# Display_Board_v3.net
KiCad netlist of a schematic drawn in EAGLE
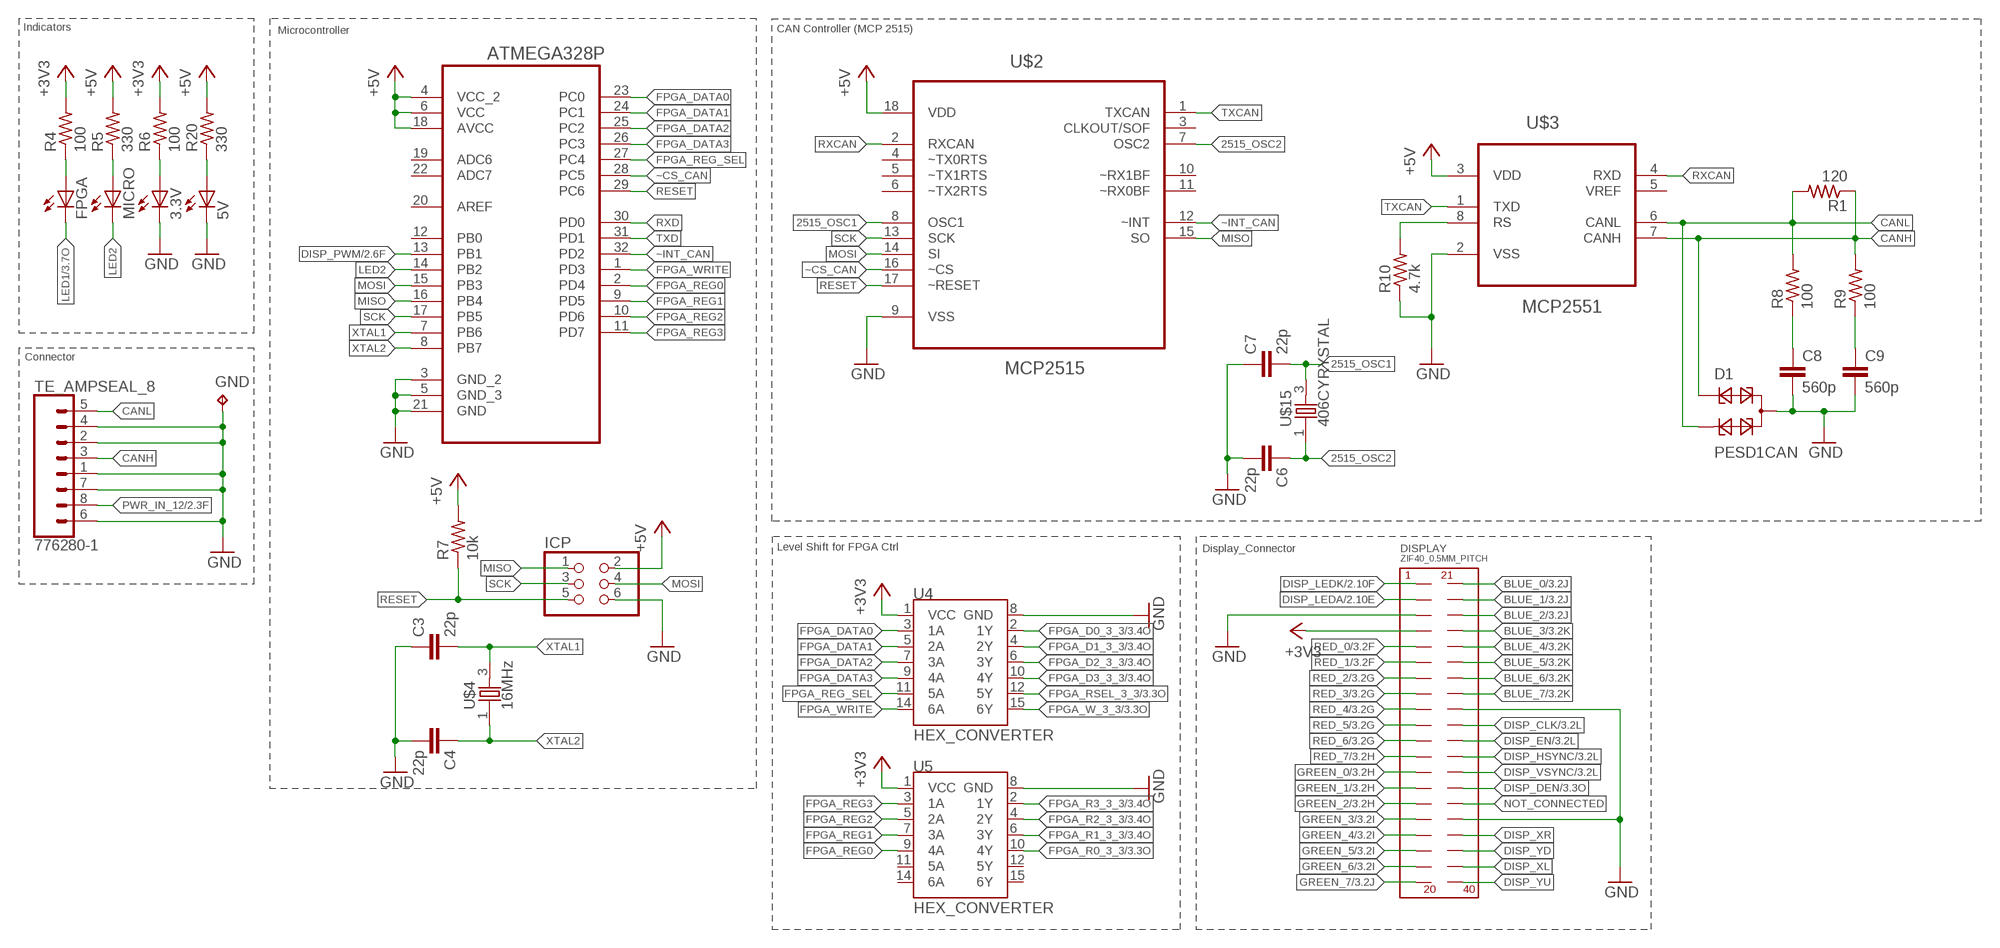
[diagram p0: schematic, sheet 1]
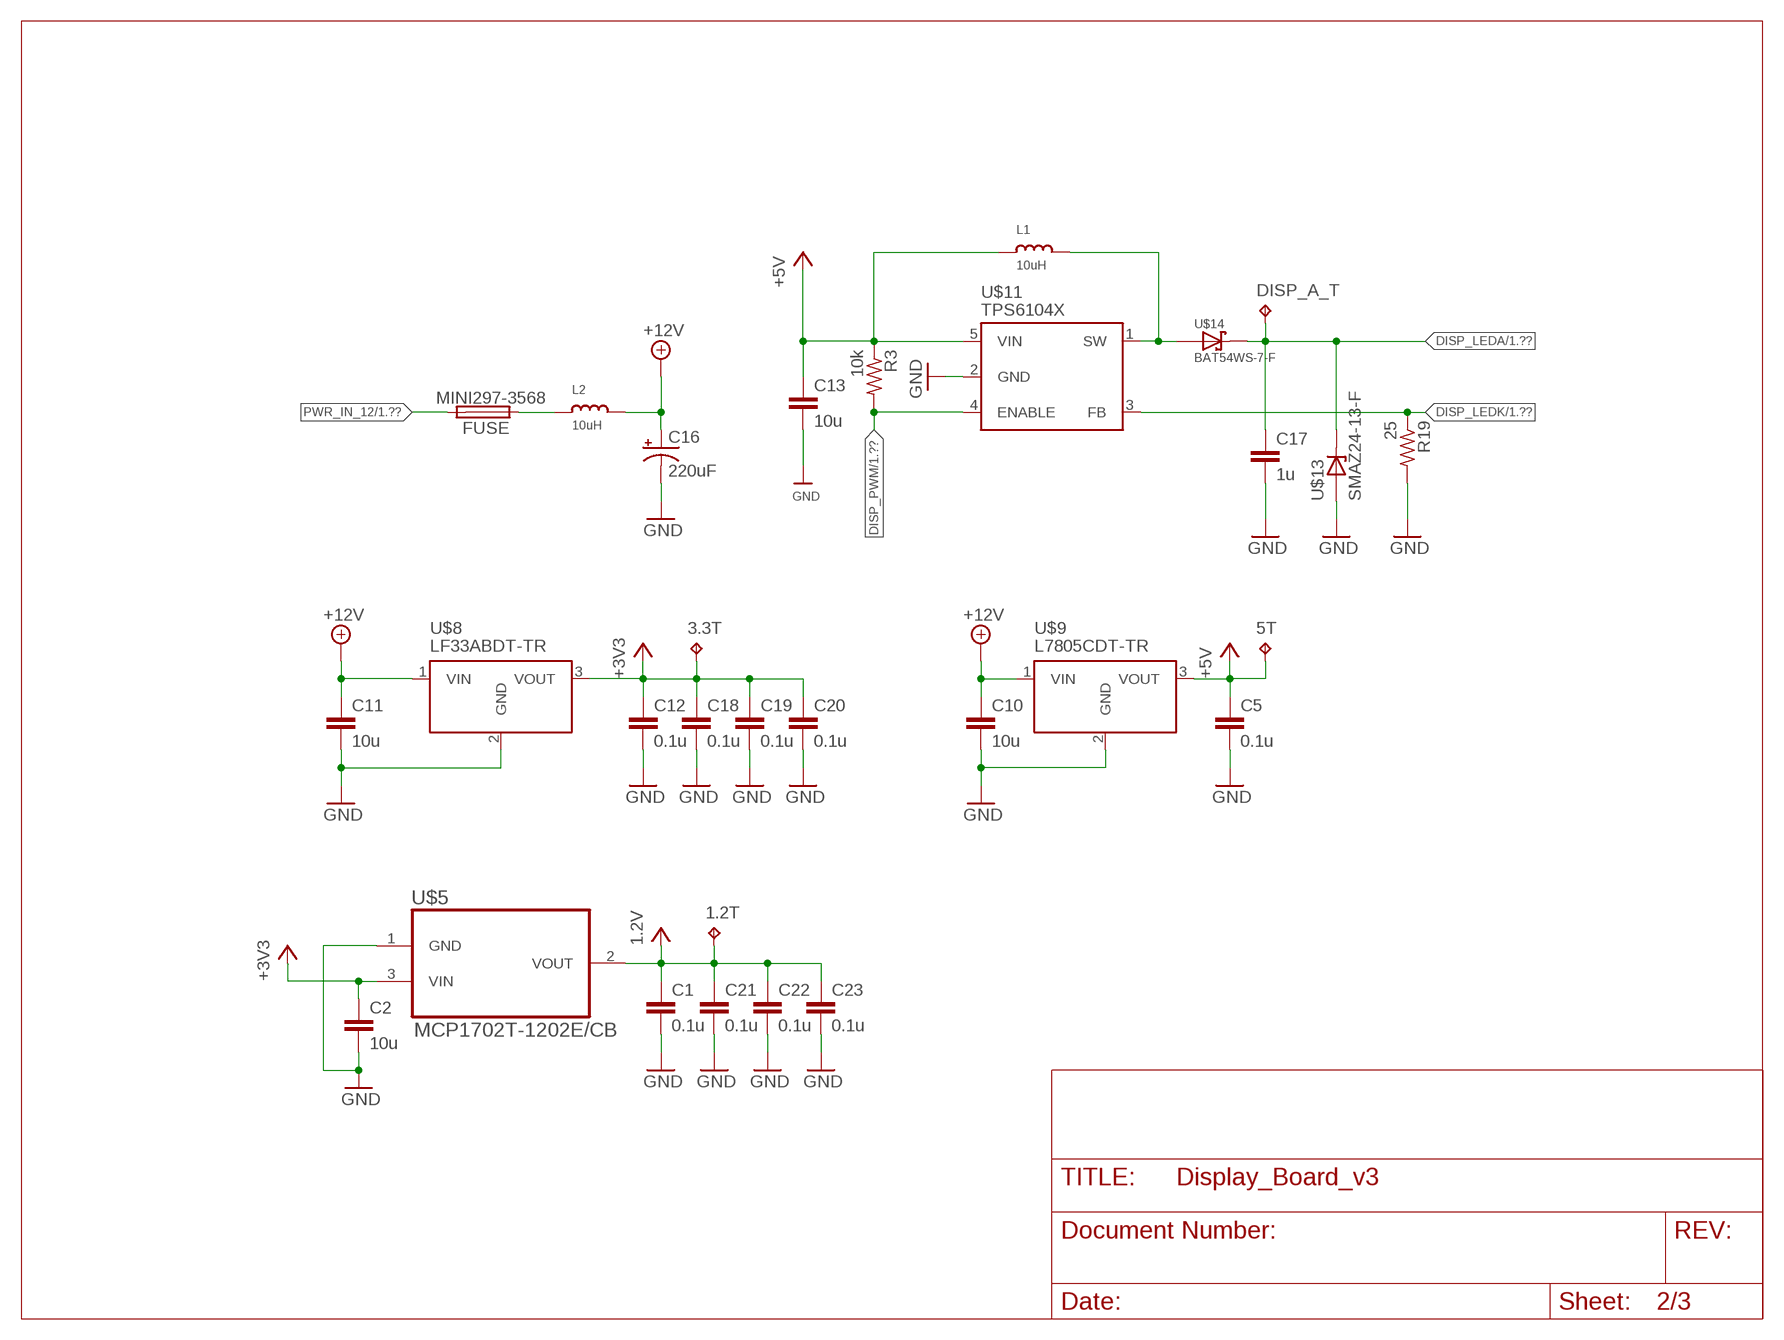
[diagram p1: schematic, sheet 2]
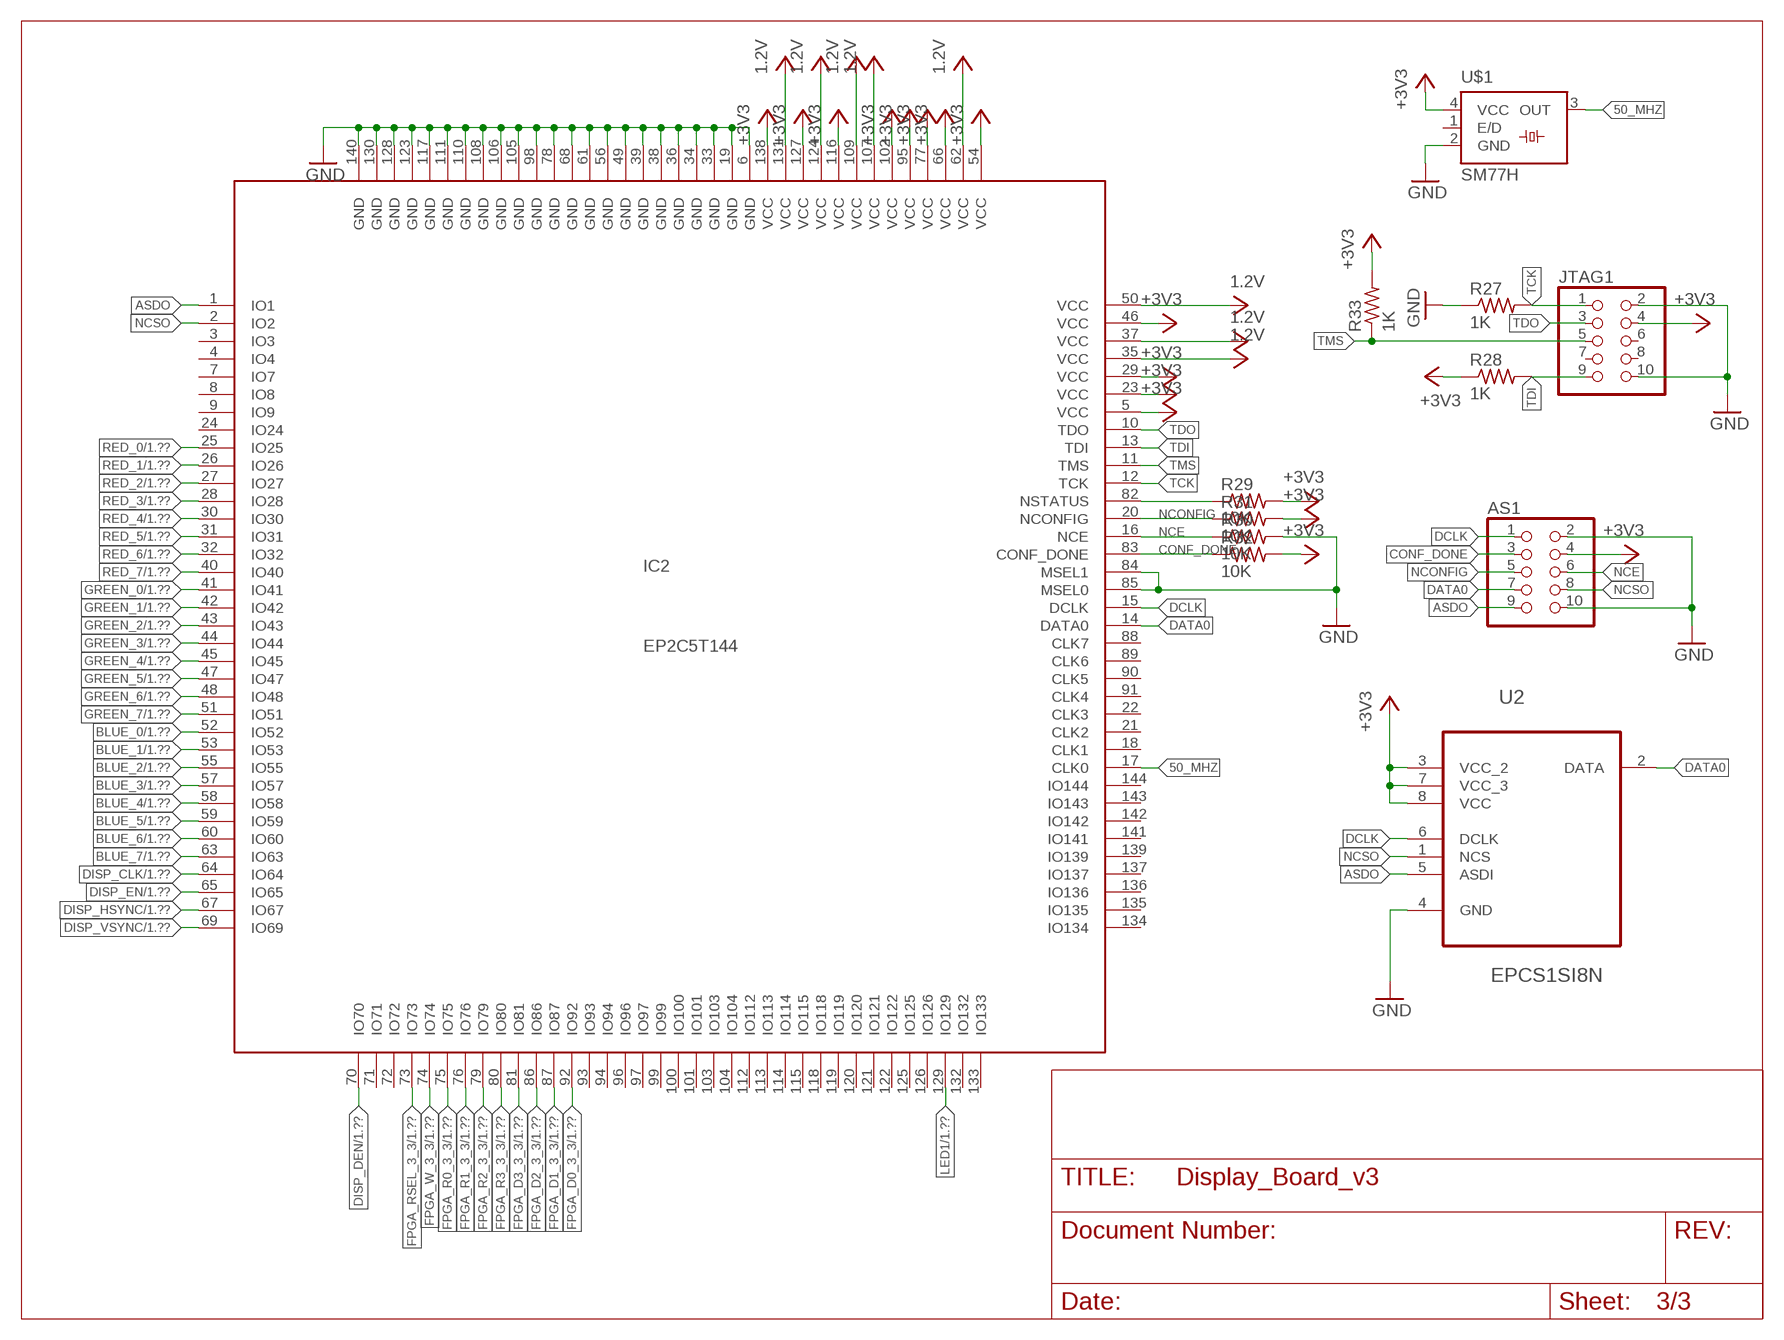
[diagram p2: schematic, sheet 3]

(export (version "E")
  (design (tool "Eeschema 10.0.6"))
  (components
    (comp (ref "3.3V")
      (value "LEDCHIP-LED0805")
      (footprint "eagle-import:CHIP-LED0805")
      (libsource (lib "eagle-import") (part "LEDCHIP-LED0805"))
    )
    (comp (ref "5V")
      (value "LEDCHIP-LED0805")
      (footprint "eagle-import:CHIP-LED0805")
      (libsource (lib "eagle-import") (part "LEDCHIP-LED0805"))
    )
    (comp (ref "ATMEGA328P")
      (value "ATMEGA328P-AU")
      (footprint "eagle-import:QFP80P900X900X120-32N")
      (libsource (lib "eagle-import") (part "ATMEGA328P-AU"))
    )
    (comp (ref "C3")
      (value "22p")
      (footprint "eagle-import:C0805K")
      (libsource (lib "eagle-import") (part "resistor_C-EUC0805K"))
    )
    (comp (ref "C4")
      (value "22p")
      (footprint "eagle-import:C0805K")
      (libsource (lib "eagle-import") (part "resistor_C-EUC0805K"))
    )
    (comp (ref "C6")
      (value "22p")
      (footprint "eagle-import:C0805K")
      (libsource (lib "eagle-import") (part "resistor_C-EUC0805K"))
    )
    (comp (ref "C7")
      (value "22p")
      (footprint "eagle-import:C0805K")
      (libsource (lib "eagle-import") (part "resistor_C-EUC0805K"))
    )
    (comp (ref "C8")
      (value "560p")
      (footprint "eagle-import:C0805K")
      (libsource (lib "eagle-import") (part "C-EUC0805K"))
    )
    (comp (ref "C9")
      (value "560p")
      (footprint "eagle-import:C0805K")
      (libsource (lib "eagle-import") (part "C-EUC0805K"))
    )
    (comp (ref "D1")
      (value "PESD1CAN")
      (footprint "eagle-import:SOT23")
      (libsource (lib "eagle-import") (part "PESD1CAN"))
    )
    (comp (ref "DISPLAY")
      (value "ZIF40_0.5MM_PITCH")
      (footprint "eagle-import:ZIF40")
      (libsource (lib "eagle-import") (part "ZIF40_0.5MM_PITCH"))
    )
    (comp (ref "FPGA")
      (value "LEDCHIP-LED0805")
      (footprint "eagle-import:CHIP-LED0805")
      (libsource (lib "eagle-import") (part "LEDCHIP-LED0805"))
    )
    (comp (ref "GND")
      (value "TPTP12SQ")
      (footprint "eagle-import:TP12SQ")
      (libsource (lib "eagle-import") (part "TPTP12SQ"))
    )
    (comp (ref "ICP")
      (value "PINHD-2X3")
      (footprint "eagle-import:2X03")
      (libsource (lib "eagle-import") (part "PINHD-2X3"))
    )
    (comp (ref "MICRO")
      (value "LEDCHIP-LED0805")
      (footprint "eagle-import:CHIP-LED0805")
      (libsource (lib "eagle-import") (part "LEDCHIP-LED0805"))
    )
    (comp (ref "R1")
      (value "120")
      (footprint "eagle-import:R0805")
      (libsource (lib "eagle-import") (part "R-US_R0805"))
    )
    (comp (ref "R4")
      (value "100")
      (footprint "eagle-import:R0805")
      (libsource (lib "eagle-import") (part "resistor_R-US_R0805"))
    )
    (comp (ref "R5")
      (value "330")
      (footprint "eagle-import:R0805")
      (libsource (lib "eagle-import") (part "resistor_R-US_R0805"))
    )
    (comp (ref "R6")
      (value "100")
      (footprint "eagle-import:R0805")
      (libsource (lib "eagle-import") (part "resistor_R-US_R0805"))
    )
    (comp (ref "R7")
      (value "10k")
      (footprint "eagle-import:R0805")
      (libsource (lib "eagle-import") (part "R-US_R0805"))
    )
    (comp (ref "R8")
      (value "100")
      (footprint "eagle-import:R0805")
      (libsource (lib "eagle-import") (part "R-US_R0805"))
    )
    (comp (ref "R9")
      (value "100")
      (footprint "eagle-import:R0805")
      (libsource (lib "eagle-import") (part "R-US_R0805"))
    )
    (comp (ref "R10")
      (value "4.7k")
      (footprint "eagle-import:R0805")
      (libsource (lib "eagle-import") (part "R-US_R0805"))
    )
    (comp (ref "R20")
      (value "330")
      (footprint "eagle-import:R0805")
      (libsource (lib "eagle-import") (part "resistor_R-US_R0805"))
    )
    (comp (ref "TE_AMPSEAL_8")
      (value "776280-1")
      (footprint "eagle-import:776280-1")
      (libsource (lib "eagle-import") (part "776280-1"))
    )
    (comp (ref "U$2")
      (value "MCP2515")
      (footprint "eagle-import:SOIC127P1034X264-18N")
      (fields (field (name "MPN") "MCP2515-I/SO"))
      (libsource (lib "eagle-import") (part "MCP2515-I/SO"))
    )
    (comp (ref "U$3")
      (value "MCP2551")
      (footprint "eagle-import:SOIC127P600X175-8N")
      (fields (field (name "MPN") "MCP2551-I/SN"))
      (libsource (lib "eagle-import") (part "MCP2551-I/SN"))
    )
    (comp (ref "U$4")
      (value "16MHz")
      (footprint "eagle-import:CTS406")
      (libsource (lib "eagle-import") (part "406CYRYSTAL"))
    )
    (comp (ref "U$15")
      (value "406CYRYSTAL")
      (footprint "eagle-import:CTS406")
      (libsource (lib "eagle-import") (part "406CYRYSTAL"))
    )
    (comp (ref "U4")
      (value "HEX_CONVERTER")
      (footprint "eagle-import:SO016")
      (libsource (lib "eagle-import") (part "HEX_CONVERTER"))
    )
    (comp (ref "U5")
      (value "HEX_CONVERTER")
      (footprint "eagle-import:SO016")
      (libsource (lib "eagle-import") (part "HEX_CONVERTER"))
    )
    (comp (ref "AS1")
      (value "PINHD-2X5")
      (footprint "eagle-import:2X05")
      (libsource (lib "eagle-import") (part "PINHD-2X5"))
    )
    (comp (ref "IC2")
      (value "EP2C5T144")
      (footprint "eagle-import:TQFP144")
      (fields (field (name "MPN") "EP2C5T144C8N"))
      (libsource (lib "eagle-import") (part "EP2C5T144"))
    )
    (comp (ref "JTAG1")
      (value "PINHD-2X5")
      (footprint "eagle-import:2X05")
      (libsource (lib "eagle-import") (part "PINHD-2X5"))
    )
    (comp (ref "R27")
      (value "1K")
      (footprint "eagle-import:R0805")
      (libsource (lib "eagle-import") (part "resistor_R-US_R0805"))
    )
    (comp (ref "R28")
      (value "1K")
      (footprint "eagle-import:R0805")
      (libsource (lib "eagle-import") (part "resistor_R-US_R0805"))
    )
    (comp (ref "R29")
      (value "10K")
      (footprint "eagle-import:R0805")
      (libsource (lib "eagle-import") (part "resistor_R-US_R0805"))
    )
    (comp (ref "R30")
      (value "10K")
      (footprint "eagle-import:R0805")
      (libsource (lib "eagle-import") (part "resistor_R-US_R0805"))
    )
    (comp (ref "R31")
      (value "10K")
      (footprint "eagle-import:R0805")
      (libsource (lib "eagle-import") (part "resistor_R-US_R0805"))
    )
    (comp (ref "R32")
      (value "10K")
      (footprint "eagle-import:R0805")
      (libsource (lib "eagle-import") (part "resistor_R-US_R0805"))
    )
    (comp (ref "R33")
      (value "1K")
      (footprint "eagle-import:R0805")
      (libsource (lib "eagle-import") (part "resistor_R-US_R0805"))
    )
    (comp (ref "U$1")
      (value "SM77H")
      (footprint "eagle-import:SM77H")
      (libsource (lib "eagle-import") (part "SM77H"))
    )
    (comp (ref "U2")
      (value "EPCS1SI8N")
      (footprint "eagle-import:SOIC127P600X175-8N")
      (libsource (lib "eagle-import") (part "EPCS1SI8N"))
    )
    (comp (ref "1.2T")
      (value "TPTP12SQ")
      (footprint "eagle-import:TP12SQ")
      (libsource (lib "eagle-import") (part "TPTP12SQ"))
    )
    (comp (ref "3.3T")
      (value "TPTP12SQ")
      (footprint "eagle-import:TP12SQ")
      (libsource (lib "eagle-import") (part "TPTP12SQ"))
    )
    (comp (ref "5T")
      (value "TPTP12SQ")
      (footprint "eagle-import:TP12SQ")
      (libsource (lib "eagle-import") (part "TPTP12SQ"))
    )
    (comp (ref "C1")
      (value "0.1u")
      (footprint "eagle-import:C0805K")
      (libsource (lib "eagle-import") (part "C-EUC0805K"))
    )
    (comp (ref "C2")
      (value "10u")
      (footprint "eagle-import:C0805K")
      (libsource (lib "eagle-import") (part "C-EUC0805K"))
    )
    (comp (ref "C5")
      (value "0.1u")
      (footprint "eagle-import:C0805K")
      (libsource (lib "eagle-import") (part "C-EUC0805K"))
    )
    (comp (ref "C10")
      (value "10u")
      (footprint "eagle-import:C0805K")
      (libsource (lib "eagle-import") (part "C-EUC0805K"))
    )
    (comp (ref "C11")
      (value "10u")
      (footprint "eagle-import:C0805K")
      (libsource (lib "eagle-import") (part "C-EUC0805K"))
    )
    (comp (ref "C12")
      (value "0.1u")
      (footprint "eagle-import:C0805K")
      (libsource (lib "eagle-import") (part "C-EUC0805K"))
    )
    (comp (ref "C13")
      (value "10u")
      (footprint "eagle-import:C0805K")
      (libsource (lib "eagle-import") (part "C-EUC0805K"))
    )
    (comp (ref "C16")
      (value "220uF")
      (footprint "eagle-import:UD-6,3X7,7_NICHICON")
      (libsource (lib "eagle-import") (part "CPOL-USUD-6,3X7,7"))
    )
    (comp (ref "C17")
      (value "1u")
      (footprint "eagle-import:C0805K")
      (libsource (lib "eagle-import") (part "C-EUC0805K"))
    )
    (comp (ref "C18")
      (value "0.1u")
      (footprint "eagle-import:C0805K")
      (libsource (lib "eagle-import") (part "C-EUC0805K"))
    )
    (comp (ref "C19")
      (value "0.1u")
      (footprint "eagle-import:C0805K")
      (libsource (lib "eagle-import") (part "C-EUC0805K"))
    )
    (comp (ref "C20")
      (value "0.1u")
      (footprint "eagle-import:C0805K")
      (libsource (lib "eagle-import") (part "C-EUC0805K"))
    )
    (comp (ref "C21")
      (value "0.1u")
      (footprint "eagle-import:C0805K")
      (libsource (lib "eagle-import") (part "C-EUC0805K"))
    )
    (comp (ref "C22")
      (value "0.1u")
      (footprint "eagle-import:C0805K")
      (libsource (lib "eagle-import") (part "C-EUC0805K"))
    )
    (comp (ref "C23")
      (value "0.1u")
      (footprint "eagle-import:C0805K")
      (libsource (lib "eagle-import") (part "C-EUC0805K"))
    )
    (comp (ref "DISP_A_T")
      (value "TPTP12SQ")
      (footprint "eagle-import:TP12SQ")
      (libsource (lib "eagle-import") (part "TPTP12SQ"))
    )
    (comp (ref "FUSE")
      (value "MINI297-3568")
      (footprint "eagle-import:3568")
      (libsource (lib "eagle-import") (part "MINI297-3568"))
    )
    (comp (ref "L1")
      (value "10uH")
      (footprint "eagle-import:INDUCTOR_5X5MM_NR5040_NOTHERMALS")
      (libsource (lib "eagle-import") (part "INDUCTORNR5040"))
    )
    (comp (ref "L2")
      (value "10uH")
      (footprint "eagle-import:INDUCTOR_5X5MM_NR5040_NOTHERMALS")
      (libsource (lib "eagle-import") (part "INDUCTORNR5040"))
    )
    (comp (ref "R3")
      (value "10k")
      (footprint "eagle-import:R0805")
      (libsource (lib "eagle-import") (part "rcl_334_R-US_R0805"))
    )
    (comp (ref "R19")
      (value "25")
      (footprint "eagle-import:R0805")
      (libsource (lib "eagle-import") (part "rcl_334_R-US_R0805"))
    )
    (comp (ref "U$5")
      (value "MCP1702T-1202E/CB")
      (footprint "eagle-import:SOT95P300X145-3N")
      (fields (field (name "MPN") "MCP1702T-1802E/CB"))
      (libsource (lib "eagle-import") (part "MCP1702T-1802E/CB"))
    )
    (comp (ref "U$8")
      (value "LF33ABDT-TR")
      (footprint "eagle-import:DPACK")
      (libsource (lib "eagle-import") (part "LF33ABDT-TR"))
    )
    (comp (ref "U$9")
      (value "L7805CDT-TR")
      (footprint "eagle-import:DPACK")
      (libsource (lib "eagle-import") (part "L7805CDT-TR"))
    )
    (comp (ref "U$11")
      (value "TPS6104X")
      (footprint "eagle-import:SOT23-5L")
      (libsource (lib "eagle-import") (part "TPS6104X"))
    )
    (comp (ref "U$13")
      (value "SMAZ24-13-F")
      (footprint "eagle-import:SMA_DIODE")
      (libsource (lib "eagle-import") (part "SMAZ24-13-F"))
    )
    (comp (ref "U$14")
      (value "BAT54WS-7-F")
      (footprint "eagle-import:SOD323")
      (libsource (lib "eagle-import") (part "BAT54WS-7-F"))
    )
  )
  (nets
    (net (code "1") (name "+3V3") (class "Default")
      (node (ref "3.3T") (pin "TP") (pinfunction "TP_TP") (pintype "input"))
      (node (ref "AS1") (pin "4") (pinfunction "4_4") (pintype "passive"))
      (node (ref "C12") (pin "1") (pinfunction "1_1") (pintype "passive"))
      (node (ref "C18") (pin "1") (pinfunction "1_1") (pintype "passive"))
      (node (ref "C19") (pin "1") (pinfunction "1_1") (pintype "passive"))
      (node (ref "C2") (pin "1") (pinfunction "1_1") (pintype "passive"))
      (node (ref "C20") (pin "1") (pinfunction "1_1") (pintype "passive"))
      (node (ref "DISPLAY") (pin "P$4") (pinfunction "P$4_P$4") (pintype "bidirectional"))
      (node (ref "IC2") (pin "102") (pinfunction "VCC_102") (pintype "power_in"))
      (node (ref "IC2") (pin "116") (pinfunction "VCC_116") (pintype "power_in"))
      (node (ref "IC2") (pin "127") (pinfunction "VCC_127") (pintype "power_in"))
      (node (ref "IC2") (pin "138") (pinfunction "VCC_138") (pintype "power_in"))
      (node (ref "IC2") (pin "23") (pinfunction "VCC_23") (pintype "power_in"))
      (node (ref "IC2") (pin "29") (pinfunction "VCC_29") (pintype "power_in"))
      (node (ref "IC2") (pin "46") (pinfunction "VCC_46") (pintype "power_in"))
      (node (ref "IC2") (pin "5") (pinfunction "VCC_5") (pintype "power_in"))
      (node (ref "IC2") (pin "54") (pinfunction "VCC_54") (pintype "power_in"))
      (node (ref "IC2") (pin "66") (pinfunction "VCC_66") (pintype "power_in"))
      (node (ref "IC2") (pin "77") (pinfunction "VCC_77") (pintype "power_in"))
      (node (ref "IC2") (pin "95") (pinfunction "VCC_95") (pintype "power_in"))
      (node (ref "JTAG1") (pin "4") (pinfunction "4_4") (pintype "passive"))
      (node (ref "R28") (pin "1") (pinfunction "1_1") (pintype "passive"))
      (node (ref "R29") (pin "2") (pinfunction "2_2") (pintype "passive"))
      (node (ref "R31") (pin "2") (pinfunction "2_2") (pintype "passive"))
      (node (ref "R32") (pin "2") (pinfunction "2_2") (pintype "passive"))
      (node (ref "R33") (pin "2") (pinfunction "2_2") (pintype "passive"))
      (node (ref "R4") (pin "2") (pinfunction "2_2") (pintype "passive"))
      (node (ref "R6") (pin "2") (pinfunction "2_2") (pintype "passive"))
      (node (ref "U$1") (pin "4") (pinfunction "VCC_4") (pintype "power_in"))
      (node (ref "U$5") (pin "3") (pinfunction "VIN_3") (pintype "power_in"))
      (node (ref "U$8") (pin "3") (pinfunction "VOUT_3") (pintype "bidirectional"))
      (node (ref "U2") (pin "3") (pinfunction "VCC_2_3") (pintype "power_in"))
      (node (ref "U2") (pin "7") (pinfunction "VCC_3_7") (pintype "power_in"))
      (node (ref "U2") (pin "8") (pinfunction "VCC_8") (pintype "power_in"))
      (node (ref "U4") (pin "1") (pinfunction "VCC_1") (pintype "bidirectional"))
      (node (ref "U5") (pin "1") (pinfunction "VCC_1") (pintype "bidirectional"))
    )
    (net (code "2") (name "+5V") (class "Default")
      (node (ref "5T") (pin "TP") (pinfunction "TP_TP") (pintype "input"))
      (node (ref "ATMEGA328P") (pin "18") (pinfunction "AVCC_18") (pintype "power_in"))
      (node (ref "ATMEGA328P") (pin "4") (pinfunction "VCC_2_4") (pintype "power_in"))
      (node (ref "ATMEGA328P") (pin "6") (pinfunction "VCC_6") (pintype "power_in"))
      (node (ref "C13") (pin "1") (pinfunction "1_1") (pintype "passive"))
      (node (ref "C5") (pin "1") (pinfunction "1_1") (pintype "passive"))
      (node (ref "ICP") (pin "2") (pinfunction "2_2") (pintype "passive"))
      (node (ref "L1") (pin "P$1") (pinfunction "1_P$1") (pintype "passive"))
      (node (ref "R20") (pin "2") (pinfunction "2_2") (pintype "passive"))
      (node (ref "R3") (pin "1") (pinfunction "1_1") (pintype "passive"))
      (node (ref "R5") (pin "2") (pinfunction "2_2") (pintype "passive"))
      (node (ref "R7") (pin "2") (pinfunction "2_2") (pintype "passive"))
      (node (ref "U$11") (pin "5") (pinfunction "VIN_5") (pintype "bidirectional"))
      (node (ref "U$2") (pin "18") (pinfunction "VDD_18") (pintype "power_in"))
      (node (ref "U$3") (pin "3") (pinfunction "VDD_3") (pintype "power_in"))
      (node (ref "U$9") (pin "3") (pinfunction "VOUT_3") (pintype "bidirectional"))
    )
    (net (code "3") (name "+12V") (class "Default")
      (node (ref "C10") (pin "1") (pinfunction "1_1") (pintype "passive"))
      (node (ref "C11") (pin "1") (pinfunction "1_1") (pintype "passive"))
      (node (ref "C16") (pin "+") (pinfunction "+_+") (pintype "passive"))
      (node (ref "L2") (pin "P$2") (pinfunction "2_P$2") (pintype "passive"))
      (node (ref "U$8") (pin "1") (pinfunction "VIN_1") (pintype "bidirectional"))
      (node (ref "U$9") (pin "1") (pinfunction "VIN_1") (pintype "bidirectional"))
    )
    (net (code "4") (name "50_MHZ") (class "Default")
      (node (ref "IC2") (pin "17") (pinfunction "CLK0_17") (pintype "bidirectional"))
      (node (ref "U$1") (pin "3") (pinfunction "OUT_3") (pintype "output"))
    )
    (net (code "5") (name "2515_OSC1") (class "Default")
      (node (ref "C7") (pin "2") (pinfunction "2_2") (pintype "passive"))
      (node (ref "U$15") (pin "3") (pinfunction "2_3") (pintype "passive"))
      (node (ref "U$2") (pin "8") (pinfunction "OSC1_8") (pintype "input"))
    )
    (net (code "6") (name "2515_OSC2") (class "Default")
      (node (ref "C6") (pin "1") (pinfunction "1_1") (pintype "passive"))
      (node (ref "U$15") (pin "1") (pinfunction "1_1") (pintype "passive"))
      (node (ref "U$2") (pin "7") (pinfunction "OSC2_7") (pintype "output"))
    )
    (net (code "7") (name "ASDO") (class "Default")
      (node (ref "AS1") (pin "9") (pinfunction "9_9") (pintype "passive"))
      (node (ref "IC2") (pin "1") (pinfunction "IO1_1") (pintype "output"))
      (node (ref "U2") (pin "5") (pinfunction "ASDI_5") (pintype "input"))
    )
    (net (code "8") (name "BLUE_0") (class "Default")
      (node (ref "DISPLAY") (pin "P$21") (pinfunction "P$21_P$21") (pintype "bidirectional"))
      (node (ref "IC2") (pin "52") (pinfunction "IO52_52") (pintype "bidirectional"))
    )
    (net (code "9") (name "BLUE_1") (class "Default")
      (node (ref "DISPLAY") (pin "P$22") (pinfunction "P$22_P$22") (pintype "bidirectional"))
      (node (ref "IC2") (pin "53") (pinfunction "IO53_53") (pintype "bidirectional"))
    )
    (net (code "10") (name "BLUE_2") (class "Default")
      (node (ref "DISPLAY") (pin "P$23") (pinfunction "P$23_P$23") (pintype "bidirectional"))
      (node (ref "IC2") (pin "55") (pinfunction "IO55_55") (pintype "bidirectional"))
    )
    (net (code "11") (name "BLUE_3") (class "Default")
      (node (ref "DISPLAY") (pin "P$24") (pinfunction "P$24_P$24") (pintype "bidirectional"))
      (node (ref "IC2") (pin "57") (pinfunction "IO57_57") (pintype "bidirectional"))
    )
    (net (code "12") (name "BLUE_4") (class "Default")
      (node (ref "DISPLAY") (pin "P$25") (pinfunction "P$25_P$25") (pintype "bidirectional"))
      (node (ref "IC2") (pin "58") (pinfunction "IO58_58") (pintype "bidirectional"))
    )
    (net (code "13") (name "BLUE_5") (class "Default")
      (node (ref "DISPLAY") (pin "P$26") (pinfunction "P$26_P$26") (pintype "bidirectional"))
      (node (ref "IC2") (pin "59") (pinfunction "IO59_59") (pintype "bidirectional"))
    )
    (net (code "14") (name "BLUE_6") (class "Default")
      (node (ref "DISPLAY") (pin "P$27") (pinfunction "P$27_P$27") (pintype "bidirectional"))
      (node (ref "IC2") (pin "60") (pinfunction "IO60_60") (pintype "bidirectional"))
    )
    (net (code "15") (name "BLUE_7") (class "Default")
      (node (ref "DISPLAY") (pin "P$28") (pinfunction "P$28_P$28") (pintype "bidirectional"))
      (node (ref "IC2") (pin "63") (pinfunction "IO63_63") (pintype "bidirectional"))
    )
    (net (code "16") (name "CANH") (class "Default")
      (node (ref "D1") (pin "1") (pinfunction "1_1") (pintype "passive"))
      (node (ref "R1") (pin "1") (pinfunction "1_1") (pintype "passive"))
      (node (ref "R9") (pin "2") (pinfunction "2_2") (pintype "passive"))
      (node (ref "TE_AMPSEAL_8") (pin "3") (pinfunction "5_3") (pintype "passive"))
      (node (ref "U$3") (pin "7") (pinfunction "CANH_7") (pintype "bidirectional"))
    )
    (net (code "17") (name "CANL") (class "Default")
      (node (ref "D1") (pin "2") (pinfunction "2_2") (pintype "passive"))
      (node (ref "R1") (pin "2") (pinfunction "2_2") (pintype "passive"))
      (node (ref "R8") (pin "2") (pinfunction "2_2") (pintype "passive"))
      (node (ref "TE_AMPSEAL_8") (pin "5") (pinfunction "8_5") (pintype "passive"))
      (node (ref "U$3") (pin "6") (pinfunction "CANL_6") (pintype "bidirectional"))
    )
    (net (code "18") (name "CONF_DONE") (class "Default")
      (node (ref "AS1") (pin "3") (pinfunction "3_3") (pintype "passive"))
      (node (ref "IC2") (pin "83") (pinfunction "CONF_DONE_83") (pintype "input"))
      (node (ref "R32") (pin "1") (pinfunction "1_1") (pintype "passive"))
    )
    (net (code "19") (name "DATA0") (class "Default")
      (node (ref "AS1") (pin "7") (pinfunction "7_7") (pintype "passive"))
      (node (ref "IC2") (pin "14") (pinfunction "DATA0_14") (pintype "bidirectional"))
      (node (ref "U2") (pin "2") (pinfunction "DATA_2") (pintype "output"))
    )
    (net (code "20") (name "DCLK") (class "Default")
      (node (ref "AS1") (pin "1") (pinfunction "1_1") (pintype "passive"))
      (node (ref "IC2") (pin "15") (pinfunction "DCLK_15") (pintype "bidirectional"))
      (node (ref "U2") (pin "6") (pinfunction "DCLK_6") (pintype "input"))
    )
    (net (code "21") (name "DISP_CLK") (class "Default")
      (node (ref "DISPLAY") (pin "P$30") (pinfunction "P$30_P$30") (pintype "bidirectional"))
      (node (ref "IC2") (pin "64") (pinfunction "IO64_64") (pintype "bidirectional"))
    )
    (net (code "22") (name "DISP_DEN") (class "Default")
      (node (ref "DISPLAY") (pin "P$34") (pinfunction "P$34_P$34") (pintype "bidirectional"))
      (node (ref "IC2") (pin "70") (pinfunction "IO70_70") (pintype "bidirectional"))
    )
    (net (code "23") (name "DISP_EN") (class "Default")
      (node (ref "DISPLAY") (pin "P$31") (pinfunction "P$31_P$31") (pintype "bidirectional"))
      (node (ref "IC2") (pin "65") (pinfunction "IO65_65") (pintype "bidirectional"))
    )
    (net (code "24") (name "DISP_HSYNC") (class "Default")
      (node (ref "DISPLAY") (pin "P$32") (pinfunction "P$32_P$32") (pintype "bidirectional"))
      (node (ref "IC2") (pin "67") (pinfunction "IO67_67") (pintype "bidirectional"))
    )
    (net (code "25") (name "DISP_LEDA") (class "Default")
      (node (ref "C17") (pin "1") (pinfunction "1_1") (pintype "passive"))
      (node (ref "DISPLAY") (pin "P$2") (pinfunction "P$2_P$2") (pintype "bidirectional"))
      (node (ref "DISP_A_T") (pin "TP") (pinfunction "TP_TP") (pintype "input"))
      (node (ref "U$13") (pin "C") (pinfunction "C_C") (pintype "bidirectional"))
      (node (ref "U$14") (pin "1") (pinfunction "C_1") (pintype "bidirectional"))
    )
    (net (code "26") (name "DISP_LEDK") (class "Default")
      (node (ref "DISPLAY") (pin "P$1") (pinfunction "P$1_P$1") (pintype "bidirectional"))
      (node (ref "R19") (pin "1") (pinfunction "1_1") (pintype "passive"))
      (node (ref "U$11") (pin "3") (pinfunction "FB_3") (pintype "bidirectional"))
    )
    (net (code "27") (name "DISP_PWM") (class "Default")
      (node (ref "ATMEGA328P") (pin "13") (pinfunction "PB1_13") (pintype "bidirectional"))
      (node (ref "R3") (pin "2") (pinfunction "2_2") (pintype "passive"))
      (node (ref "U$11") (pin "4") (pinfunction "ENABLE_4") (pintype "bidirectional"))
    )
    (net (code "28") (name "DISP_VSYNC") (class "Default")
      (node (ref "DISPLAY") (pin "P$33") (pinfunction "P$33_P$33") (pintype "bidirectional"))
      (node (ref "IC2") (pin "69") (pinfunction "IO69_69") (pintype "bidirectional"))
    )
    (net (code "29") (name "DISP_XL") (class "Default")
      (node (ref "DISPLAY") (pin "P$39") (pinfunction "P$39_P$39") (pintype "bidirectional"))
    )
    (net (code "30") (name "DISP_XR") (class "Default")
      (node (ref "DISPLAY") (pin "P$37") (pinfunction "P$37_P$37") (pintype "bidirectional"))
    )
    (net (code "31") (name "DISP_YD") (class "Default")
      (node (ref "DISPLAY") (pin "P$38") (pinfunction "P$38_P$38") (pintype "bidirectional"))
    )
    (net (code "32") (name "DISP_YU") (class "Default")
      (node (ref "DISPLAY") (pin "P$40") (pinfunction "P$40_P$40") (pintype "bidirectional"))
    )
    (net (code "33") (name "FPGA_D0_3_3") (class "Default")
      (node (ref "IC2") (pin "92") (pinfunction "IO92_92") (pintype "bidirectional"))
      (node (ref "U4") (pin "2") (pinfunction "1Y_2") (pintype "bidirectional"))
    )
    (net (code "34") (name "FPGA_D1_3_3") (class "Default")
      (node (ref "IC2") (pin "87") (pinfunction "IO87_87") (pintype "bidirectional"))
      (node (ref "U4") (pin "4") (pinfunction "2Y_4") (pintype "bidirectional"))
    )
    (net (code "35") (name "FPGA_D2_3_3") (class "Default")
      (node (ref "IC2") (pin "86") (pinfunction "IO86_86") (pintype "bidirectional"))
      (node (ref "U4") (pin "6") (pinfunction "3Y_6") (pintype "bidirectional"))
    )
    (net (code "36") (name "FPGA_D3_3_3") (class "Default")
      (node (ref "IC2") (pin "81") (pinfunction "IO81_81") (pintype "bidirectional"))
      (node (ref "U4") (pin "10") (pinfunction "4Y_10") (pintype "bidirectional"))
    )
    (net (code "37") (name "FPGA_DATA0") (class "Default")
      (node (ref "ATMEGA328P") (pin "23") (pinfunction "PC0_23") (pintype "bidirectional"))
      (node (ref "U4") (pin "3") (pinfunction "1A_3") (pintype "bidirectional"))
    )
    (net (code "38") (name "FPGA_DATA1") (class "Default")
      (node (ref "ATMEGA328P") (pin "24") (pinfunction "PC1_24") (pintype "bidirectional"))
      (node (ref "U4") (pin "5") (pinfunction "2A_5") (pintype "bidirectional"))
    )
    (net (code "39") (name "FPGA_DATA2") (class "Default")
      (node (ref "ATMEGA328P") (pin "25") (pinfunction "PC2_25") (pintype "bidirectional"))
      (node (ref "U4") (pin "7") (pinfunction "3A_7") (pintype "bidirectional"))
    )
    (net (code "40") (name "FPGA_DATA3") (class "Default")
      (node (ref "ATMEGA328P") (pin "26") (pinfunction "PC3_26") (pintype "bidirectional"))
      (node (ref "U4") (pin "9") (pinfunction "4A_9") (pintype "bidirectional"))
    )
    (net (code "41") (name "FPGA_R0_3_3") (class "Default")
      (node (ref "IC2") (pin "75") (pinfunction "IO75_75") (pintype "bidirectional"))
      (node (ref "U5") (pin "10") (pinfunction "4Y_10") (pintype "bidirectional"))
    )
    (net (code "42") (name "FPGA_R1_3_3") (class "Default")
      (node (ref "IC2") (pin "76") (pinfunction "IO76_76") (pintype "bidirectional"))
      (node (ref "U5") (pin "6") (pinfunction "3Y_6") (pintype "bidirectional"))
    )
    (net (code "43") (name "FPGA_R2_3_3") (class "Default")
      (node (ref "IC2") (pin "79") (pinfunction "IO79_79") (pintype "bidirectional"))
      (node (ref "U5") (pin "4") (pinfunction "2Y_4") (pintype "bidirectional"))
    )
    (net (code "44") (name "FPGA_R3_3_3") (class "Default")
      (node (ref "IC2") (pin "80") (pinfunction "IO80_80") (pintype "bidirectional"))
      (node (ref "U5") (pin "2") (pinfunction "1Y_2") (pintype "bidirectional"))
    )
    (net (code "45") (name "FPGA_REG0") (class "Default")
      (node (ref "ATMEGA328P") (pin "2") (pinfunction "PD4_2") (pintype "bidirectional"))
      (node (ref "U5") (pin "9") (pinfunction "4A_9") (pintype "bidirectional"))
    )
    (net (code "46") (name "FPGA_REG1") (class "Default")
      (node (ref "ATMEGA328P") (pin "9") (pinfunction "PD5_9") (pintype "bidirectional"))
      (node (ref "U5") (pin "7") (pinfunction "3A_7") (pintype "bidirectional"))
    )
    (net (code "47") (name "FPGA_REG2") (class "Default")
      (node (ref "ATMEGA328P") (pin "10") (pinfunction "PD6_10") (pintype "bidirectional"))
      (node (ref "U5") (pin "5") (pinfunction "2A_5") (pintype "bidirectional"))
    )
    (net (code "48") (name "FPGA_REG3") (class "Default")
      (node (ref "ATMEGA328P") (pin "11") (pinfunction "PD7_11") (pintype "bidirectional"))
      (node (ref "U5") (pin "3") (pinfunction "1A_3") (pintype "bidirectional"))
    )
    (net (code "49") (name "FPGA_REG_SEL") (class "Default")
      (node (ref "ATMEGA328P") (pin "27") (pinfunction "PC4_27") (pintype "bidirectional"))
      (node (ref "U4") (pin "11") (pinfunction "5A_11") (pintype "bidirectional"))
    )
    (net (code "50") (name "FPGA_RSEL_3_3") (class "Default")
      (node (ref "IC2") (pin "73") (pinfunction "IO73_73") (pintype "bidirectional"))
      (node (ref "U4") (pin "12") (pinfunction "5Y_12") (pintype "bidirectional"))
    )
    (net (code "51") (name "FPGA_WRITE") (class "Default")
      (node (ref "ATMEGA328P") (pin "1") (pinfunction "PD3_1") (pintype "bidirectional"))
      (node (ref "U4") (pin "14") (pinfunction "6A_14") (pintype "bidirectional"))
    )
    (net (code "52") (name "FPGA_W_3_3") (class "Default")
      (node (ref "IC2") (pin "74") (pinfunction "IO74_74") (pintype "bidirectional"))
      (node (ref "U4") (pin "15") (pinfunction "6Y_15") (pintype "bidirectional"))
    )
    (net (code "53") (name "GND") (class "Default")
      (node (ref "3.3V") (pin "C") (pinfunction "C_C") (pintype "passive"))
      (node (ref "5V") (pin "C") (pinfunction "C_C") (pintype "passive"))
      (node (ref "AS1") (pin "10") (pinfunction "10_10") (pintype "passive"))
      (node (ref "AS1") (pin "2") (pinfunction "2_2") (pintype "passive"))
      (node (ref "ATMEGA328P") (pin "21") (pinfunction "GND_21") (pintype "passive"))
      (node (ref "ATMEGA328P") (pin "3") (pinfunction "GND_2_3") (pintype "passive"))
      (node (ref "ATMEGA328P") (pin "5") (pinfunction "GND_3_5") (pintype "passive"))
      (node (ref "C1") (pin "2") (pinfunction "2_2") (pintype "passive"))
      (node (ref "C10") (pin "2") (pinfunction "2_2") (pintype "passive"))
      (node (ref "C11") (pin "2") (pinfunction "2_2") (pintype "passive"))
      (node (ref "C12") (pin "2") (pinfunction "2_2") (pintype "passive"))
      (node (ref "C13") (pin "2") (pinfunction "2_2") (pintype "passive"))
      (node (ref "C16") (pin "-") (pinfunction "-_-") (pintype "passive"))
      (node (ref "C17") (pin "2") (pinfunction "2_2") (pintype "passive"))
      (node (ref "C18") (pin "2") (pinfunction "2_2") (pintype "passive"))
      (node (ref "C19") (pin "2") (pinfunction "2_2") (pintype "passive"))
      (node (ref "C2") (pin "2") (pinfunction "2_2") (pintype "passive"))
      (node (ref "C20") (pin "2") (pinfunction "2_2") (pintype "passive"))
      (node (ref "C21") (pin "2") (pinfunction "2_2") (pintype "passive"))
      (node (ref "C22") (pin "2") (pinfunction "2_2") (pintype "passive"))
      (node (ref "C23") (pin "2") (pinfunction "2_2") (pintype "passive"))
      (node (ref "C3") (pin "1") (pinfunction "1_1") (pintype "passive"))
      (node (ref "C4") (pin "2") (pinfunction "2_2") (pintype "passive"))
      (node (ref "C5") (pin "2") (pinfunction "2_2") (pintype "passive"))
      (node (ref "C6") (pin "2") (pinfunction "2_2") (pintype "passive"))
      (node (ref "C7") (pin "1") (pinfunction "1_1") (pintype "passive"))
      (node (ref "C8") (pin "2") (pinfunction "2_2") (pintype "passive"))
      (node (ref "C9") (pin "2") (pinfunction "2_2") (pintype "passive"))
      (node (ref "D1") (pin "3") (pinfunction "3_3") (pintype "passive"))
      (node (ref "DISPLAY") (pin "P$29") (pinfunction "P$29_P$29") (pintype "bidirectional"))
      (node (ref "DISPLAY") (pin "P$3") (pinfunction "P$3_P$3") (pintype "bidirectional"))
      (node (ref "DISPLAY") (pin "P$36") (pinfunction "P$36_P$36") (pintype "bidirectional"))
      (node (ref "GND") (pin "TP") (pinfunction "TP_TP") (pintype "input"))
      (node (ref "IC2") (pin "105") (pinfunction "GND_105") (pintype "power_in"))
      (node (ref "IC2") (pin "106") (pinfunction "GND_106") (pintype "power_in"))
      (node (ref "IC2") (pin "108") (pinfunction "GND_108") (pintype "power_in"))
      (node (ref "IC2") (pin "110") (pinfunction "GND_110") (pintype "power_in"))
      (node (ref "IC2") (pin "111") (pinfunction "GND_111") (pintype "power_in"))
      (node (ref "IC2") (pin "117") (pinfunction "GND_117") (pintype "power_in"))
      (node (ref "IC2") (pin "123") (pinfunction "GND_123") (pintype "power_in"))
      (node (ref "IC2") (pin "128") (pinfunction "GND_128") (pintype "power_in"))
      (node (ref "IC2") (pin "130") (pinfunction "GND_130") (pintype "power_in"))
      (node (ref "IC2") (pin "140") (pinfunction "GND_140") (pintype "power_in"))
      (node (ref "IC2") (pin "19") (pinfunction "GND_19") (pintype "power_in"))
      (node (ref "IC2") (pin "33") (pinfunction "GND_33") (pintype "power_in"))
      (node (ref "IC2") (pin "34") (pinfunction "GND_34") (pintype "power_in"))
      (node (ref "IC2") (pin "36") (pinfunction "GND_36") (pintype "power_in"))
      (node (ref "IC2") (pin "38") (pinfunction "GND_38") (pintype "power_in"))
      (node (ref "IC2") (pin "39") (pinfunction "GND_39") (pintype "power_in"))
      (node (ref "IC2") (pin "49") (pinfunction "GND_49") (pintype "power_in"))
      (node (ref "IC2") (pin "56") (pinfunction "GND_56") (pintype "power_in"))
      (node (ref "IC2") (pin "6") (pinfunction "GND_6") (pintype "power_in"))
      (node (ref "IC2") (pin "61") (pinfunction "GND_61") (pintype "power_in"))
      (node (ref "IC2") (pin "68") (pinfunction "GND_68") (pintype "power_in"))
      (node (ref "IC2") (pin "78") (pinfunction "GND_78") (pintype "power_in"))
      (node (ref "IC2") (pin "84") (pinfunction "MSEL1_84") (pintype "input"))
      (node (ref "IC2") (pin "85") (pinfunction "MSEL0_85") (pintype "input"))
      (node (ref "IC2") (pin "98") (pinfunction "GND_98") (pintype "power_in"))
      (node (ref "ICP") (pin "6") (pinfunction "6_6") (pintype "passive"))
      (node (ref "JTAG1") (pin "10") (pinfunction "10_10") (pintype "passive"))
      (node (ref "JTAG1") (pin "2") (pinfunction "2_2") (pintype "passive"))
      (node (ref "R10") (pin "1") (pinfunction "1_1") (pintype "passive"))
      (node (ref "R19") (pin "2") (pinfunction "2_2") (pintype "passive"))
      (node (ref "R27") (pin "1") (pinfunction "1_1") (pintype "passive"))
      (node (ref "R30") (pin "2") (pinfunction "2_2") (pintype "passive"))
      (node (ref "TE_AMPSEAL_8") (pin "1") (pinfunction "4_1") (pintype "passive"))
      (node (ref "TE_AMPSEAL_8") (pin "2") (pinfunction "6_2") (pintype "passive"))
      (node (ref "TE_AMPSEAL_8") (pin "4") (pinfunction "7_4") (pintype "passive"))
      (node (ref "TE_AMPSEAL_8") (pin "6") (pinfunction "1_6") (pintype "passive"))
      (node (ref "TE_AMPSEAL_8") (pin "7") (pinfunction "3_7") (pintype "passive"))
      (node (ref "U$1") (pin "2") (pinfunction "GND_2") (pintype "power_in"))
      (node (ref "U$11") (pin "2") (pinfunction "GND_2") (pintype "bidirectional"))
      (node (ref "U$13") (pin "A") (pinfunction "A_A") (pintype "input"))
      (node (ref "U$2") (pin "9") (pinfunction "VSS_9") (pintype "power_in"))
      (node (ref "U$3") (pin "2") (pinfunction "VSS_2") (pintype "passive"))
      (node (ref "U$5") (pin "1") (pinfunction "GND_1") (pintype "passive"))
      (node (ref "U$8") (pin "2") (pinfunction "GND_2") (pintype "bidirectional"))
      (node (ref "U$9") (pin "2") (pinfunction "GND_2") (pintype "bidirectional"))
      (node (ref "U2") (pin "4") (pinfunction "GND_4") (pintype "passive"))
      (node (ref "U4") (pin "8") (pinfunction "GND_8") (pintype "bidirectional"))
      (node (ref "U5") (pin "8") (pinfunction "GND_8") (pintype "bidirectional"))
    )
    (net (code "54") (name "GREEN_0") (class "Default")
      (node (ref "DISPLAY") (pin "P$13") (pinfunction "P$13_P$13") (pintype "bidirectional"))
      (node (ref "IC2") (pin "41") (pinfunction "IO41_41") (pintype "bidirectional"))
    )
    (net (code "55") (name "GREEN_1") (class "Default")
      (node (ref "DISPLAY") (pin "P$14") (pinfunction "P$14_P$14") (pintype "bidirectional"))
      (node (ref "IC2") (pin "42") (pinfunction "IO42_42") (pintype "bidirectional"))
    )
    (net (code "56") (name "GREEN_2") (class "Default")
      (node (ref "DISPLAY") (pin "P$15") (pinfunction "P$15_P$15") (pintype "bidirectional"))
      (node (ref "IC2") (pin "43") (pinfunction "IO43_43") (pintype "bidirectional"))
    )
    (net (code "57") (name "GREEN_3") (class "Default")
      (node (ref "DISPLAY") (pin "P$16") (pinfunction "P$16_P$16") (pintype "bidirectional"))
      (node (ref "IC2") (pin "44") (pinfunction "IO44_44") (pintype "bidirectional"))
    )
    (net (code "58") (name "GREEN_4") (class "Default")
      (node (ref "DISPLAY") (pin "P$17") (pinfunction "P$17_P$17") (pintype "bidirectional"))
      (node (ref "IC2") (pin "45") (pinfunction "IO45_45") (pintype "bidirectional"))
    )
    (net (code "59") (name "GREEN_5") (class "Default")
      (node (ref "DISPLAY") (pin "P$18") (pinfunction "P$18_P$18") (pintype "bidirectional"))
      (node (ref "IC2") (pin "47") (pinfunction "IO47_47") (pintype "bidirectional"))
    )
    (net (code "60") (name "GREEN_6") (class "Default")
      (node (ref "DISPLAY") (pin "P$19") (pinfunction "P$19_P$19") (pintype "bidirectional"))
      (node (ref "IC2") (pin "48") (pinfunction "IO48_48") (pintype "bidirectional"))
    )
    (net (code "61") (name "GREEN_7") (class "Default")
      (node (ref "DISPLAY") (pin "P$20") (pinfunction "P$20_P$20") (pintype "bidirectional"))
      (node (ref "IC2") (pin "51") (pinfunction "IO51_51") (pintype "bidirectional"))
    )
    (net (code "62") (name "LED1") (class "Default")
      (node (ref "FPGA") (pin "C") (pinfunction "C_C") (pintype "passive"))
      (node (ref "IC2") (pin "129") (pinfunction "IO129_129") (pintype "bidirectional"))
    )
    (net (code "63") (name "LED2") (class "Default")
      (node (ref "ATMEGA328P") (pin "14") (pinfunction "PB2_14") (pintype "bidirectional"))
      (node (ref "MICRO") (pin "C") (pinfunction "C_C") (pintype "passive"))
    )
    (net (code "64") (name "MISO") (class "Default")
      (node (ref "ATMEGA328P") (pin "16") (pinfunction "PB4_16") (pintype "bidirectional"))
      (node (ref "ICP") (pin "1") (pinfunction "1_1") (pintype "passive"))
      (node (ref "U$2") (pin "15") (pinfunction "SO_15") (pintype "output"))
    )
    (net (code "65") (name "MOSI") (class "Default")
      (node (ref "ATMEGA328P") (pin "15") (pinfunction "PB3_15") (pintype "bidirectional"))
      (node (ref "ICP") (pin "4") (pinfunction "4_4") (pintype "passive"))
      (node (ref "U$2") (pin "14") (pinfunction "SI_14") (pintype "input"))
    )
    (net (code "66") (name "NCE") (class "Default")
      (node (ref "AS1") (pin "6") (pinfunction "6_6") (pintype "passive"))
      (node (ref "IC2") (pin "16") (pinfunction "NCE_16") (pintype "input"))
      (node (ref "R30") (pin "1") (pinfunction "1_1") (pintype "passive"))
    )
    (net (code "67") (name "NCONFIG") (class "Default")
      (node (ref "AS1") (pin "5") (pinfunction "5_5") (pintype "passive"))
      (node (ref "IC2") (pin "20") (pinfunction "NCONFIG_20") (pintype "input"))
      (node (ref "R31") (pin "1") (pinfunction "1_1") (pintype "passive"))
    )
    (net (code "68") (name "NCSO") (class "Default")
      (node (ref "AS1") (pin "8") (pinfunction "8_8") (pintype "passive"))
      (node (ref "IC2") (pin "2") (pinfunction "IO2_2") (pintype "output"))
      (node (ref "U2") (pin "1") (pinfunction "NCS_1") (pintype "input"))
    )
    (net (code "69") (name "NOT_CONNECTED") (class "Default")
      (node (ref "DISPLAY") (pin "P$35") (pinfunction "P$35_P$35") (pintype "bidirectional"))
    )
    (net (code "70") (name "Net-(3.3V-PadA)") (class "Default")
      (node (ref "3.3V") (pin "A") (pinfunction "A_A") (pintype "passive"))
      (node (ref "R6") (pin "1") (pinfunction "1_1") (pintype "passive"))
    )
    (net (code "71") (name "Net-(5V-PadA)") (class "Default")
      (node (ref "5V") (pin "A") (pinfunction "A_A") (pintype "passive"))
      (node (ref "R20") (pin "1") (pinfunction "1_1") (pintype "passive"))
    )
    (net (code "72") (name "Net-(C8-Pad1)") (class "Default")
      (node (ref "C8") (pin "1") (pinfunction "1_1") (pintype "passive"))
      (node (ref "R8") (pin "1") (pinfunction "1_1") (pintype "passive"))
    )
    (net (code "73") (name "Net-(C9-Pad1)") (class "Default")
      (node (ref "C9") (pin "1") (pinfunction "1_1") (pintype "passive"))
      (node (ref "R9") (pin "1") (pinfunction "1_1") (pintype "passive"))
    )
    (net (code "74") (name "Net-(FPGA-PadA)") (class "Default")
      (node (ref "FPGA") (pin "A") (pinfunction "A_A") (pintype "passive"))
      (node (ref "R4") (pin "1") (pinfunction "1_1") (pintype "passive"))
    )
    (net (code "75") (name "Net-(IC2-NSTATUS)") (class "Default")
      (node (ref "IC2") (pin "82") (pinfunction "NSTATUS_82") (pintype "input"))
      (node (ref "R29") (pin "1") (pinfunction "1_1") (pintype "passive"))
    )
    (net (code "76") (name "Net-(L1-2)") (class "Default")
      (node (ref "L1") (pin "P$2") (pinfunction "2_P$2") (pintype "passive"))
      (node (ref "U$11") (pin "1") (pinfunction "SW_1") (pintype "bidirectional"))
      (node (ref "U$14") (pin "2") (pinfunction "A_2") (pintype "bidirectional"))
    )
    (net (code "77") (name "Net-(L2-1)") (class "Default")
      (node (ref "FUSE") (pin "P$1") (pinfunction "1_P$1") (pintype "passive"))
      (node (ref "FUSE") (pin "P$4") (pinfunction "1_P$4") (pintype "passive"))
      (node (ref "L2") (pin "P$1") (pinfunction "1_P$1") (pintype "passive"))
    )
    (net (code "78") (name "Net-(MICRO-PadA)") (class "Default")
      (node (ref "MICRO") (pin "A") (pinfunction "A_A") (pintype "passive"))
      (node (ref "R5") (pin "1") (pinfunction "1_1") (pintype "passive"))
    )
    (net (code "79") (name "Net-(U$3-RS)") (class "Default")
      (node (ref "R10") (pin "2") (pinfunction "2_2") (pintype "passive"))
      (node (ref "U$3") (pin "8") (pinfunction "RS_8") (pintype "input"))
    )
    (net (code "80") (name "PWR_IN_12") (class "Default")
      (node (ref "FUSE") (pin "P$2") (pinfunction "2_P$2") (pintype "passive"))
      (node (ref "FUSE") (pin "P$3") (pinfunction "2_P$3") (pintype "passive"))
      (node (ref "TE_AMPSEAL_8") (pin "8") (pinfunction "2_8") (pintype "passive"))
    )
    (net (code "81") (name "RED_0") (class "Default")
      (node (ref "DISPLAY") (pin "P$5") (pinfunction "P$5_P$5") (pintype "bidirectional"))
      (node (ref "IC2") (pin "25") (pinfunction "IO25_25") (pintype "bidirectional"))
    )
    (net (code "82") (name "RED_1") (class "Default")
      (node (ref "DISPLAY") (pin "P$6") (pinfunction "P$6_P$6") (pintype "bidirectional"))
      (node (ref "IC2") (pin "26") (pinfunction "IO26_26") (pintype "bidirectional"))
    )
    (net (code "83") (name "RED_2") (class "Default")
      (node (ref "DISPLAY") (pin "P$7") (pinfunction "P$7_P$7") (pintype "bidirectional"))
      (node (ref "IC2") (pin "27") (pinfunction "IO27_27") (pintype "bidirectional"))
    )
    (net (code "84") (name "RED_3") (class "Default")
      (node (ref "DISPLAY") (pin "P$8") (pinfunction "P$8_P$8") (pintype "bidirectional"))
      (node (ref "IC2") (pin "28") (pinfunction "IO28_28") (pintype "bidirectional"))
    )
    (net (code "85") (name "RED_4") (class "Default")
      (node (ref "DISPLAY") (pin "P$9") (pinfunction "P$9_P$9") (pintype "bidirectional"))
      (node (ref "IC2") (pin "30") (pinfunction "IO30_30") (pintype "bidirectional"))
    )
    (net (code "86") (name "RED_5") (class "Default")
      (node (ref "DISPLAY") (pin "P$10") (pinfunction "P$10_P$10") (pintype "bidirectional"))
      (node (ref "IC2") (pin "31") (pinfunction "IO31_31") (pintype "bidirectional"))
    )
    (net (code "87") (name "RED_6") (class "Default")
      (node (ref "DISPLAY") (pin "P$11") (pinfunction "P$11_P$11") (pintype "bidirectional"))
      (node (ref "IC2") (pin "32") (pinfunction "IO32_32") (pintype "bidirectional"))
    )
    (net (code "88") (name "RED_7") (class "Default")
      (node (ref "DISPLAY") (pin "P$12") (pinfunction "P$12_P$12") (pintype "bidirectional"))
      (node (ref "IC2") (pin "40") (pinfunction "IO40_40") (pintype "bidirectional"))
    )
    (net (code "89") (name "RESET") (class "Default")
      (node (ref "ATMEGA328P") (pin "29") (pinfunction "PC6_29") (pintype "bidirectional"))
      (node (ref "ICP") (pin "5") (pinfunction "5_5") (pintype "passive"))
      (node (ref "R7") (pin "1") (pinfunction "1_1") (pintype "passive"))
      (node (ref "U$2") (pin "17") (pinfunction "~{RESET}_17") (pintype "input"))
    )
    (net (code "90") (name "RXCAN") (class "Default")
      (node (ref "U$2") (pin "2") (pinfunction "RXCAN_2") (pintype "input"))
      (node (ref "U$3") (pin "4") (pinfunction "RXD_4") (pintype "output"))
    )
    (net (code "91") (name "RXD") (class "Default")
      (node (ref "ATMEGA328P") (pin "30") (pinfunction "PD0_30") (pintype "bidirectional"))
    )
    (net (code "92") (name "SCK") (class "Default")
      (node (ref "ATMEGA328P") (pin "17") (pinfunction "PB5_17") (pintype "bidirectional"))
      (node (ref "ICP") (pin "3") (pinfunction "3_3") (pintype "passive"))
      (node (ref "U$2") (pin "13") (pinfunction "SCK_13") (pintype "input"))
    )
    (net (code "93") (name "TCK") (class "Default")
      (node (ref "IC2") (pin "12") (pinfunction "TCK_12") (pintype "input"))
      (node (ref "JTAG1") (pin "1") (pinfunction "1_1") (pintype "passive"))
      (node (ref "R27") (pin "2") (pinfunction "2_2") (pintype "passive"))
    )
    (net (code "94") (name "TDI") (class "Default")
      (node (ref "IC2") (pin "13") (pinfunction "TDI_13") (pintype "input"))
      (node (ref "JTAG1") (pin "9") (pinfunction "9_9") (pintype "passive"))
      (node (ref "R28") (pin "2") (pinfunction "2_2") (pintype "passive"))
    )
    (net (code "95") (name "TDO") (class "Default")
      (node (ref "IC2") (pin "10") (pinfunction "TDO_10") (pintype "output"))
      (node (ref "JTAG1") (pin "3") (pinfunction "3_3") (pintype "passive"))
    )
    (net (code "96") (name "TMS") (class "Default")
      (node (ref "IC2") (pin "11") (pinfunction "TMS_11") (pintype "input"))
      (node (ref "JTAG1") (pin "5") (pinfunction "5_5") (pintype "passive"))
      (node (ref "R33") (pin "1") (pinfunction "1_1") (pintype "passive"))
    )
    (net (code "97") (name "TXCAN") (class "Default")
      (node (ref "U$2") (pin "1") (pinfunction "TXCAN_1") (pintype "output"))
      (node (ref "U$3") (pin "1") (pinfunction "TXD_1") (pintype "input"))
    )
    (net (code "98") (name "TXD") (class "Default")
      (node (ref "ATMEGA328P") (pin "31") (pinfunction "PD1_31") (pintype "bidirectional"))
    )
    (net (code "99") (name "VCC") (class "Default")
      (node (ref "1.2T") (pin "TP") (pinfunction "TP_TP") (pintype "input"))
      (node (ref "C1") (pin "1") (pinfunction "1_1") (pintype "passive"))
      (node (ref "C21") (pin "1") (pinfunction "1_1") (pintype "passive"))
      (node (ref "C22") (pin "1") (pinfunction "1_1") (pintype "passive"))
      (node (ref "C23") (pin "1") (pinfunction "1_1") (pintype "passive"))
      (node (ref "IC2") (pin "107") (pinfunction "VCC_107") (pintype "power_in"))
      (node (ref "IC2") (pin "109") (pinfunction "VCC_109") (pintype "power_in"))
      (node (ref "IC2") (pin "124") (pinfunction "VCC_124") (pintype "power_in"))
      (node (ref "IC2") (pin "131") (pinfunction "VCC_131") (pintype "power_in"))
      (node (ref "IC2") (pin "35") (pinfunction "VCC_35") (pintype "power_in"))
      (node (ref "IC2") (pin "37") (pinfunction "VCC_37") (pintype "power_in"))
      (node (ref "IC2") (pin "50") (pinfunction "VCC_50") (pintype "power_in"))
      (node (ref "IC2") (pin "62") (pinfunction "VCC_62") (pintype "power_in"))
      (node (ref "U$5") (pin "2") (pinfunction "VOUT_2") (pintype "output"))
    )
    (net (code "100") (name "XTAL1") (class "Default")
      (node (ref "ATMEGA328P") (pin "7") (pinfunction "PB6_7") (pintype "bidirectional"))
      (node (ref "C3") (pin "2") (pinfunction "2_2") (pintype "passive"))
      (node (ref "U$4") (pin "3") (pinfunction "2_3") (pintype "passive"))
    )
    (net (code "101") (name "XTAL2") (class "Default")
      (node (ref "ATMEGA328P") (pin "8") (pinfunction "PB7_8") (pintype "bidirectional"))
      (node (ref "C4") (pin "1") (pinfunction "1_1") (pintype "passive"))
      (node (ref "U$4") (pin "1") (pinfunction "1_1") (pintype "passive"))
    )
    (net (code "102") (name "unconnected-(ATMEGA328P-ADC6-Pad19)") (class "Default")
      (node (ref "ATMEGA328P") (pin "19") (pinfunction "ADC6_19") (pintype "input"))
    )
    (net (code "103") (name "unconnected-(ATMEGA328P-ADC7-Pad22)") (class "Default")
      (node (ref "ATMEGA328P") (pin "22") (pinfunction "ADC7_22") (pintype "input"))
    )
    (net (code "104") (name "unconnected-(ATMEGA328P-AREF-Pad20)") (class "Default")
      (node (ref "ATMEGA328P") (pin "20") (pinfunction "AREF_20") (pintype "input"))
    )
    (net (code "105") (name "unconnected-(ATMEGA328P-PB0-Pad12)") (class "Default")
      (node (ref "ATMEGA328P") (pin "12") (pinfunction "PB0_12") (pintype "bidirectional"))
    )
    (net (code "106") (name "unconnected-(IC2-CLK1-Pad18)") (class "Default")
      (node (ref "IC2") (pin "18") (pinfunction "CLK1_18") (pintype "bidirectional"))
    )
    (net (code "107") (name "unconnected-(IC2-CLK2-Pad21)") (class "Default")
      (node (ref "IC2") (pin "21") (pinfunction "CLK2_21") (pintype "bidirectional"))
    )
    (net (code "108") (name "unconnected-(IC2-CLK3-Pad22)") (class "Default")
      (node (ref "IC2") (pin "22") (pinfunction "CLK3_22") (pintype "bidirectional"))
    )
    (net (code "109") (name "unconnected-(IC2-CLK4-Pad91)") (class "Default")
      (node (ref "IC2") (pin "91") (pinfunction "CLK4_91") (pintype "bidirectional"))
    )
    (net (code "110") (name "unconnected-(IC2-CLK5-Pad90)") (class "Default")
      (node (ref "IC2") (pin "90") (pinfunction "CLK5_90") (pintype "bidirectional"))
    )
    (net (code "111") (name "unconnected-(IC2-CLK6-Pad89)") (class "Default")
      (node (ref "IC2") (pin "89") (pinfunction "CLK6_89") (pintype "bidirectional"))
    )
    (net (code "112") (name "unconnected-(IC2-CLK7-Pad88)") (class "Default")
      (node (ref "IC2") (pin "88") (pinfunction "CLK7_88") (pintype "bidirectional"))
    )
    (net (code "113") (name "unconnected-(IC2-IO3-Pad3)") (class "Default")
      (node (ref "IC2") (pin "3") (pinfunction "IO3_3") (pintype "bidirectional"))
    )
    (net (code "114") (name "unconnected-(IC2-IO4-Pad4)") (class "Default")
      (node (ref "IC2") (pin "4") (pinfunction "IO4_4") (pintype "bidirectional"))
    )
    (net (code "115") (name "unconnected-(IC2-IO7-Pad7)") (class "Default")
      (node (ref "IC2") (pin "7") (pinfunction "IO7_7") (pintype "bidirectional"))
    )
    (net (code "116") (name "unconnected-(IC2-IO8-Pad8)") (class "Default")
      (node (ref "IC2") (pin "8") (pinfunction "IO8_8") (pintype "bidirectional"))
    )
    (net (code "117") (name "unconnected-(IC2-IO9-Pad9)") (class "Default")
      (node (ref "IC2") (pin "9") (pinfunction "IO9_9") (pintype "bidirectional"))
    )
    (net (code "118") (name "unconnected-(IC2-IO24-Pad24)") (class "Default")
      (node (ref "IC2") (pin "24") (pinfunction "IO24_24") (pintype "bidirectional"))
    )
    (net (code "119") (name "unconnected-(IC2-IO71-Pad71)") (class "Default")
      (node (ref "IC2") (pin "71") (pinfunction "IO71_71") (pintype "bidirectional"))
    )
    (net (code "120") (name "unconnected-(IC2-IO72-Pad72)") (class "Default")
      (node (ref "IC2") (pin "72") (pinfunction "IO72_72") (pintype "bidirectional"))
    )
    (net (code "121") (name "unconnected-(IC2-IO93-Pad93)") (class "Default")
      (node (ref "IC2") (pin "93") (pinfunction "IO93_93") (pintype "bidirectional"))
    )
    (net (code "122") (name "unconnected-(IC2-IO94-Pad94)") (class "Default")
      (node (ref "IC2") (pin "94") (pinfunction "IO94_94") (pintype "bidirectional"))
    )
    (net (code "123") (name "unconnected-(IC2-IO96-Pad96)") (class "Default")
      (node (ref "IC2") (pin "96") (pinfunction "IO96_96") (pintype "bidirectional"))
    )
    (net (code "124") (name "unconnected-(IC2-IO97-Pad97)") (class "Default")
      (node (ref "IC2") (pin "97") (pinfunction "IO97_97") (pintype "bidirectional"))
    )
    (net (code "125") (name "unconnected-(IC2-IO99-Pad99)") (class "Default")
      (node (ref "IC2") (pin "99") (pinfunction "IO99_99") (pintype "bidirectional"))
    )
    (net (code "126") (name "unconnected-(IC2-IO100-Pad100)") (class "Default")
      (node (ref "IC2") (pin "100") (pinfunction "IO100_100") (pintype "bidirectional"))
    )
    (net (code "127") (name "unconnected-(IC2-IO101-Pad101)") (class "Default")
      (node (ref "IC2") (pin "101") (pinfunction "IO101_101") (pintype "bidirectional"))
    )
    (net (code "128") (name "unconnected-(IC2-IO103-Pad103)") (class "Default")
      (node (ref "IC2") (pin "103") (pinfunction "IO103_103") (pintype "bidirectional"))
    )
    (net (code "129") (name "unconnected-(IC2-IO104-Pad104)") (class "Default")
      (node (ref "IC2") (pin "104") (pinfunction "IO104_104") (pintype "bidirectional"))
    )
    (net (code "130") (name "unconnected-(IC2-IO112-Pad112)") (class "Default")
      (node (ref "IC2") (pin "112") (pinfunction "IO112_112") (pintype "bidirectional"))
    )
    (net (code "131") (name "unconnected-(IC2-IO113-Pad113)") (class "Default")
      (node (ref "IC2") (pin "113") (pinfunction "IO113_113") (pintype "bidirectional"))
    )
    (net (code "132") (name "unconnected-(IC2-IO114-Pad114)") (class "Default")
      (node (ref "IC2") (pin "114") (pinfunction "IO114_114") (pintype "bidirectional"))
    )
    (net (code "133") (name "unconnected-(IC2-IO115-Pad115)") (class "Default")
      (node (ref "IC2") (pin "115") (pinfunction "IO115_115") (pintype "bidirectional"))
    )
    (net (code "134") (name "unconnected-(IC2-IO118-Pad118)") (class "Default")
      (node (ref "IC2") (pin "118") (pinfunction "IO118_118") (pintype "bidirectional"))
    )
    (net (code "135") (name "unconnected-(IC2-IO119-Pad119)") (class "Default")
      (node (ref "IC2") (pin "119") (pinfunction "IO119_119") (pintype "bidirectional"))
    )
    (net (code "136") (name "unconnected-(IC2-IO120-Pad120)") (class "Default")
      (node (ref "IC2") (pin "120") (pinfunction "IO120_120") (pintype "bidirectional"))
    )
    (net (code "137") (name "unconnected-(IC2-IO121-Pad121)") (class "Default")
      (node (ref "IC2") (pin "121") (pinfunction "IO121_121") (pintype "bidirectional"))
    )
    (net (code "138") (name "unconnected-(IC2-IO122-Pad122)") (class "Default")
      (node (ref "IC2") (pin "122") (pinfunction "IO122_122") (pintype "bidirectional"))
    )
    (net (code "139") (name "unconnected-(IC2-IO125-Pad125)") (class "Default")
      (node (ref "IC2") (pin "125") (pinfunction "IO125_125") (pintype "bidirectional"))
    )
    (net (code "140") (name "unconnected-(IC2-IO126-Pad126)") (class "Default")
      (node (ref "IC2") (pin "126") (pinfunction "IO126_126") (pintype "bidirectional"))
    )
    (net (code "141") (name "unconnected-(IC2-IO132-Pad132)") (class "Default")
      (node (ref "IC2") (pin "132") (pinfunction "IO132_132") (pintype "bidirectional"))
    )
    (net (code "142") (name "unconnected-(IC2-IO133-Pad133)") (class "Default")
      (node (ref "IC2") (pin "133") (pinfunction "IO133_133") (pintype "bidirectional"))
    )
    (net (code "143") (name "unconnected-(IC2-IO134-Pad134)") (class "Default")
      (node (ref "IC2") (pin "134") (pinfunction "IO134_134") (pintype "bidirectional"))
    )
    (net (code "144") (name "unconnected-(IC2-IO135-Pad135)") (class "Default")
      (node (ref "IC2") (pin "135") (pinfunction "IO135_135") (pintype "bidirectional"))
    )
    (net (code "145") (name "unconnected-(IC2-IO136-Pad136)") (class "Default")
      (node (ref "IC2") (pin "136") (pinfunction "IO136_136") (pintype "bidirectional"))
    )
    (net (code "146") (name "unconnected-(IC2-IO137-Pad137)") (class "Default")
      (node (ref "IC2") (pin "137") (pinfunction "IO137_137") (pintype "bidirectional"))
    )
    (net (code "147") (name "unconnected-(IC2-IO139-Pad139)") (class "Default")
      (node (ref "IC2") (pin "139") (pinfunction "IO139_139") (pintype "bidirectional"))
    )
    (net (code "148") (name "unconnected-(IC2-IO141-Pad141)") (class "Default")
      (node (ref "IC2") (pin "141") (pinfunction "IO141_141") (pintype "bidirectional"))
    )
    (net (code "149") (name "unconnected-(IC2-IO142-Pad142)") (class "Default")
      (node (ref "IC2") (pin "142") (pinfunction "IO142_142") (pintype "bidirectional"))
    )
    (net (code "150") (name "unconnected-(IC2-IO143-Pad143)") (class "Default")
      (node (ref "IC2") (pin "143") (pinfunction "IO143_143") (pintype "bidirectional"))
    )
    (net (code "151") (name "unconnected-(IC2-IO144-Pad144)") (class "Default")
      (node (ref "IC2") (pin "144") (pinfunction "IO144_144") (pintype "bidirectional"))
    )
    (net (code "152") (name "unconnected-(JTAG1-Pad6)") (class "Default")
      (node (ref "JTAG1") (pin "6") (pinfunction "6_6") (pintype "passive"))
    )
    (net (code "153") (name "unconnected-(JTAG1-Pad7)") (class "Default")
      (node (ref "JTAG1") (pin "7") (pinfunction "7_7") (pintype "passive"))
    )
    (net (code "154") (name "unconnected-(JTAG1-Pad8)") (class "Default")
      (node (ref "JTAG1") (pin "8") (pinfunction "8_8") (pintype "passive"))
    )
    (net (code "155") (name "unconnected-(U$1-E{slash}D-Pad1)") (class "Default")
      (node (ref "U$1") (pin "1") (pinfunction "E/D_1") (pintype "input"))
    )
    (net (code "156") (name "unconnected-(U$2-CLKOUT{slash}SOF-Pad3)") (class "Default")
      (node (ref "U$2") (pin "3") (pinfunction "CLKOUT/SOF_3") (pintype "output"))
    )
    (net (code "157") (name "unconnected-(U$2-~{RX0BF}-Pad11)") (class "Default")
      (node (ref "U$2") (pin "11") (pinfunction "~{RX0BF}_11") (pintype "output"))
    )
    (net (code "158") (name "unconnected-(U$2-~{RX1BF}-Pad10)") (class "Default")
      (node (ref "U$2") (pin "10") (pinfunction "~{RX1BF}_10") (pintype "output"))
    )
    (net (code "159") (name "unconnected-(U$2-~{TX0RTS}-Pad4)") (class "Default")
      (node (ref "U$2") (pin "4") (pinfunction "~{TX0RTS}_4") (pintype "input"))
    )
    (net (code "160") (name "unconnected-(U$2-~{TX1RTS}-Pad5)") (class "Default")
      (node (ref "U$2") (pin "5") (pinfunction "~{TX1RTS}_5") (pintype "input"))
    )
    (net (code "161") (name "unconnected-(U$2-~{TX2RTS}-Pad6)") (class "Default")
      (node (ref "U$2") (pin "6") (pinfunction "~{TX2RTS}_6") (pintype "input"))
    )
    (net (code "162") (name "unconnected-(U$3-VREF-Pad5)") (class "Default")
      (node (ref "U$3") (pin "5") (pinfunction "VREF_5") (pintype "output"))
    )
    (net (code "163") (name "unconnected-(U5-5A-Pad11)") (class "Default")
      (node (ref "U5") (pin "11") (pinfunction "5A_11") (pintype "bidirectional"))
    )
    (net (code "164") (name "unconnected-(U5-5Y-Pad12)") (class "Default")
      (node (ref "U5") (pin "12") (pinfunction "5Y_12") (pintype "bidirectional"))
    )
    (net (code "165") (name "unconnected-(U5-6A-Pad14)") (class "Default")
      (node (ref "U5") (pin "14") (pinfunction "6A_14") (pintype "bidirectional"))
    )
    (net (code "166") (name "unconnected-(U5-6Y-Pad15)") (class "Default")
      (node (ref "U5") (pin "15") (pinfunction "6Y_15") (pintype "bidirectional"))
    )
    (net (code "167") (name "~{CS_CAN}") (class "Default")
      (node (ref "ATMEGA328P") (pin "28") (pinfunction "PC5_28") (pintype "bidirectional"))
      (node (ref "U$2") (pin "16") (pinfunction "~{CS}_16") (pintype "input"))
    )
    (net (code "168") (name "~{INT_CAN}") (class "Default")
      (node (ref "ATMEGA328P") (pin "32") (pinfunction "PD2_32") (pintype "bidirectional"))
      (node (ref "U$2") (pin "12") (pinfunction "~{INT}_12") (pintype "output"))
    )
  )
)
